# LED_12T-V2_0.net
KiCad netlist of a schematic drawn in Altium Designer
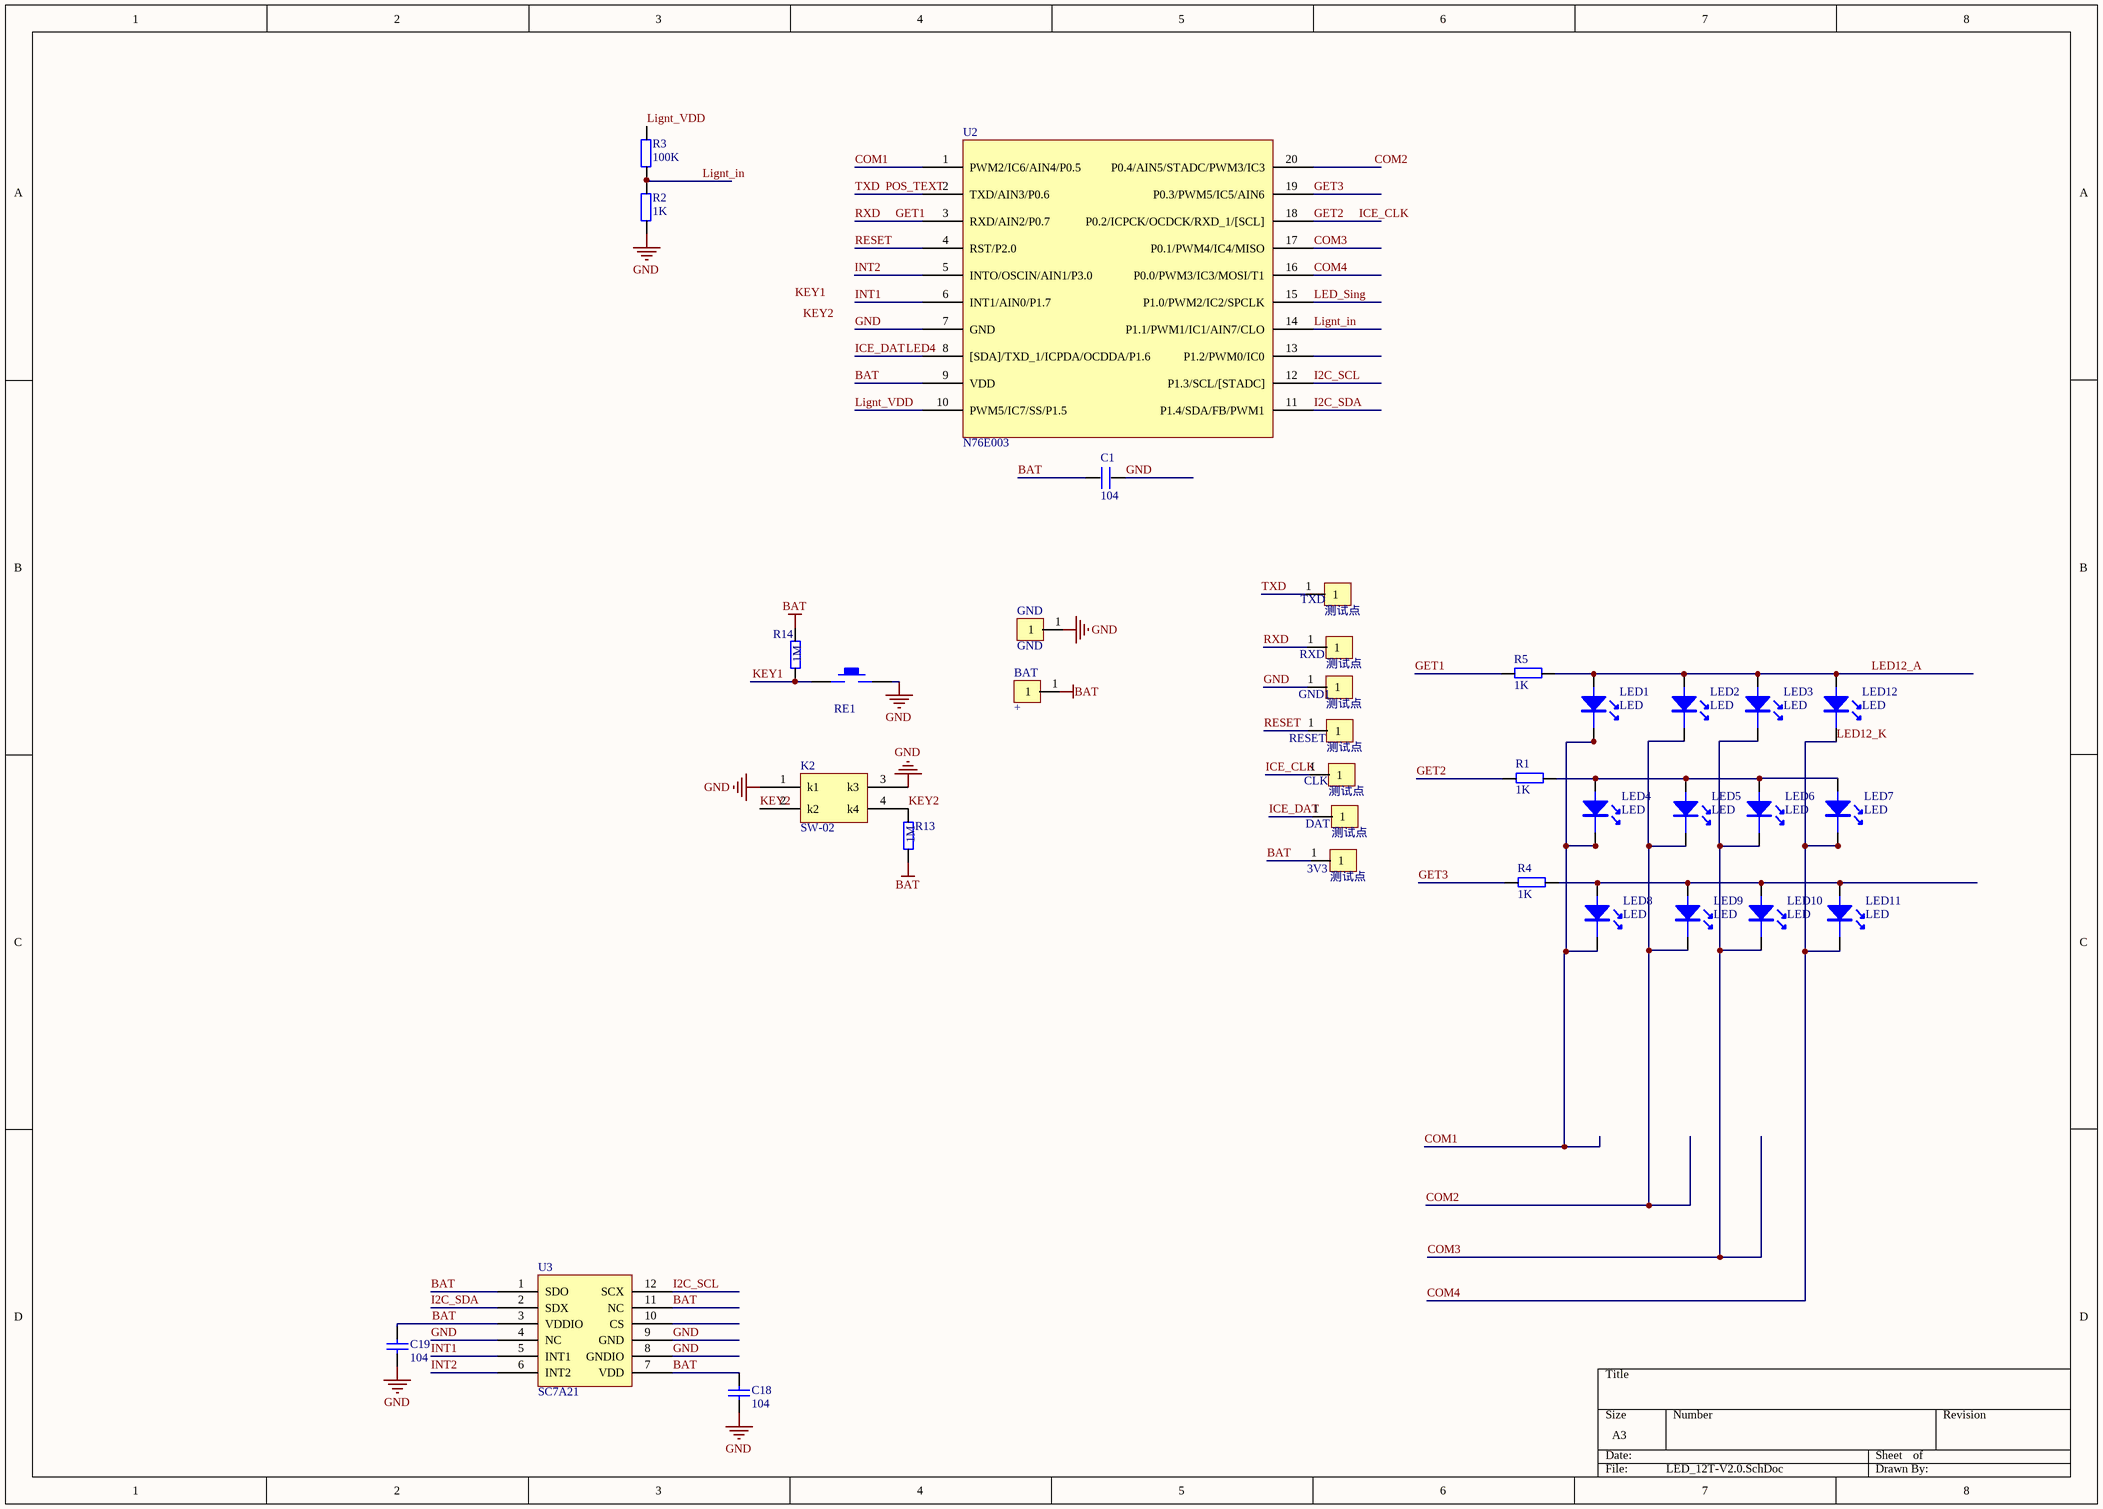
[diagram p0: LED_12T-V2.0.SchDoc]

(export (version "E")
  (design (tool "Eeschema 10.0.6"))
  (components
    (comp (ref "3V3") (value "测试点") (footprint "测试点") (libsource (lib "元件") (part "测试点")))
    (comp (ref "BAT") (value "+") (footprint "CR2450_Z") (libsource (lib "") (part "测试点_1")))
    (comp (ref "C1") (value "104") (footprint "0603P") (libsource (lib "3.5TFTLCD封装库") (part "C")))
    (comp (ref "C18")
      (value "104")
      (footprint "0402_C")
      (description "Capacitor")
      (fields (field (name "PUBLISHER") "Altium Limited"))
      (libsource (lib "Miscellaneous Devices") (part "Cap"))
    )
    (comp (ref "C19")
      (value "104")
      (footprint "0402_C")
      (description "Capacitor")
      (fields (field (name "PUBLISHER") "Altium Limited"))
      (libsource (lib "Miscellaneous Devices") (part "Cap"))
    )
    (comp (ref "CLK") (value "测试点") (footprint "测试点") (libsource (lib "元件") (part "测试点")))
    (comp (ref "DAT") (value "测试点") (footprint "测试点") (libsource (lib "元件") (part "测试点")))
    (comp (ref "GND") (value "GND") (footprint "测试点") (libsource (lib "") (part "测试点_1")))
    (comp (ref "GND1") (value "测试点") (footprint "测试点") (libsource (lib "元件") (part "测试点")))
    (comp (ref "K2") (value "SW-02") (footprint "四向滚珠开关") (libsource (lib "元件") (part "SW-02")))
    (comp (ref "LED1") (value "LED") (footprint "0402_LED") (libsource (lib "*") (part "LED")))
    (comp (ref "LED2") (value "LED") (footprint "0402_LED") (libsource (lib "*") (part "LED")))
    (comp (ref "LED3") (value "LED") (footprint "0402_LED") (libsource (lib "*") (part "LED")))
    (comp (ref "LED4") (value "LED") (footprint "0402_LED") (libsource (lib "*") (part "LED")))
    (comp (ref "LED5") (value "LED") (footprint "0402_LED") (libsource (lib "*") (part "LED")))
    (comp (ref "LED6") (value "LED") (footprint "0402_LED") (libsource (lib "*") (part "LED")))
    (comp (ref "LED7") (value "LED") (footprint "0402_LED") (libsource (lib "*") (part "LED")))
    (comp (ref "LED8") (value "LED") (footprint "0402_LED") (libsource (lib "*") (part "LED")))
    (comp (ref "LED9") (value "LED") (footprint "0402_LED") (libsource (lib "*") (part "LED")))
    (comp (ref "LED10") (value "LED") (footprint "0402_LED") (libsource (lib "*") (part "LED")))
    (comp (ref "LED11") (value "LED") (footprint "0402_LED") (libsource (lib "*") (part "LED")))
    (comp (ref "LED12") (value "LED") (footprint "0402_LED") (libsource (lib "*") (part "LED")))
    (comp (ref "R1")
      (value "1K")
      (footprint "自画库1:0603_R")
      (libsource (lib "Explorer STM32F407封装库") (part "R"))
    )
    (comp (ref "R2")
      (value "1K")
      (footprint "自画库1:0603_R")
      (libsource (lib "Explorer STM32F407封装库") (part "R"))
    )
    (comp (ref "R3")
      (value "100K")
      (footprint "自画库1:0402_R")
      (libsource (lib "Explorer STM32F407封装库") (part "R"))
    )
    (comp (ref "R4")
      (value "1K")
      (footprint "自画库1:0603_R")
      (libsource (lib "Explorer STM32F407封装库") (part "R"))
    )
    (comp (ref "R5")
      (value "1K")
      (footprint "自画库1:0603_R")
      (libsource (lib "Explorer STM32F407封装库") (part "R"))
    )
    (comp (ref "R13")
      (value "1M")
      (footprint "自画库1:0402_R")
      (libsource (lib "Explorer STM32F407封装库") (part "R"))
    )
    (comp (ref "R14")
      (value "1M")
      (footprint "自画库1:0402_R")
      (libsource (lib "Explorer STM32F407封装库") (part "R"))
    )
    (comp (ref "RE1")
      (value "KEY_M")
      (footprint "轻触开关 2x4")
      (libsource (lib "Explorer STM32F407封装库") (part "KEY_M"))
    )
    (comp (ref "RESET") (value "测试点") (footprint "测试点") (libsource (lib "元件") (part "测试点")))
    (comp (ref "RXD") (value "测试点") (footprint "测试点") (libsource (lib "元件") (part "测试点")))
    (comp (ref "TXD") (value "测试点") (footprint "测试点") (libsource (lib "元件") (part "测试点")))
    (comp (ref "U2") (value "N76E003") (footprint "STSOP20") (libsource (lib "元件") (part "N76E003")))
    (comp (ref "U3") (value "SC7A21") (footprint "自画库1:LGA-12-2*2*1") (libsource (lib "元件") (part "SC7A21")))
  )
  (nets
    (net (code "1") (name "/COM1") (class "Default")
      (node (ref "LED1") (pin "2") (pinfunction "K_2") (pintype "passive"))
      (node (ref "LED4") (pin "2") (pinfunction "K_2") (pintype "passive"))
      (node (ref "LED8") (pin "2") (pinfunction "K_2") (pintype "passive"))
      (node (ref "U2") (pin "1") (pinfunction "PWM2/IC6/AIN4/P0.5_1") (pintype "passive"))
    )
    (net (code "2") (name "/COM2") (class "Default")
      (node (ref "LED2") (pin "2") (pinfunction "K_2") (pintype "passive"))
      (node (ref "LED5") (pin "2") (pinfunction "K_2") (pintype "passive"))
      (node (ref "LED9") (pin "2") (pinfunction "K_2") (pintype "passive"))
      (node (ref "U2") (pin "20") (pinfunction "P0.4/AIN5/STADC/PWM3/IC3_20") (pintype "passive"))
    )
    (net (code "3") (name "/COM3") (class "Default")
      (node (ref "LED10") (pin "2") (pinfunction "K_2") (pintype "passive"))
      (node (ref "LED3") (pin "2") (pinfunction "K_2") (pintype "passive"))
      (node (ref "LED6") (pin "2") (pinfunction "K_2") (pintype "passive"))
      (node (ref "U2") (pin "17") (pinfunction "P0.1/PWM4/IC4/MISO_17") (pintype "passive"))
    )
    (net (code "4") (name "/COM4") (class "Default")
      (node (ref "LED11") (pin "2") (pinfunction "K_2") (pintype "passive"))
      (node (ref "LED12") (pin "2") (pinfunction "K_2") (pintype "passive"))
      (node (ref "LED7") (pin "2") (pinfunction "K_2") (pintype "passive"))
      (node (ref "U2") (pin "16") (pinfunction "P0.0/PWM3/IC3/MOSI/T1_16") (pintype "passive"))
    )
    (net (code "5") (name "/GET1") (class "Default")
      (node (ref "R5") (pin "2") (pintype "passive"))
      (node (ref "RXD") (pin "1") (pinfunction "1_1") (pintype "passive"))
      (node (ref "U2") (pin "3") (pinfunction "RXD/AIN2/P0.7_3") (pintype "passive"))
    )
    (net (code "6") (name "/GET2") (class "Default")
      (node (ref "CLK") (pin "1") (pinfunction "1_1") (pintype "passive"))
      (node (ref "R1") (pin "2") (pintype "passive"))
      (node (ref "U2") (pin "18") (pinfunction "P0.2/ICPCK/OCDCK/RXD_1/[SCL]_18") (pintype "passive"))
    )
    (net (code "7") (name "/GET3") (class "Default")
      (node (ref "R4") (pin "2") (pintype "passive"))
      (node (ref "U2") (pin "19") (pinfunction "P0.3/PWM5/IC5/AIN6_19") (pintype "passive"))
    )
    (net (code "8") (name "/I2C_SCL") (class "Default")
      (node (ref "U2") (pin "12") (pinfunction "P1.3/SCL/[STADC]_12") (pintype "passive"))
      (node (ref "U3") (pin "12") (pinfunction "SCX_12") (pintype "passive"))
    )
    (net (code "9") (name "/I2C_SDA") (class "Default")
      (node (ref "U2") (pin "11") (pinfunction "P1.4/SDA/FB/PWM1_11") (pintype "passive"))
      (node (ref "U3") (pin "2") (pinfunction "SDX_2") (pintype "passive"))
    )
    (net (code "10") (name "/ICE_DAT") (class "Default")
      (node (ref "DAT") (pin "1") (pinfunction "1_1") (pintype "passive"))
      (node (ref "U2") (pin "8") (pinfunction "[SDA]/TXD_1/ICPDA/OCDDA/P1.6_8") (pintype "passive"))
    )
    (net (code "11") (name "/INT1") (class "Default")
      (node (ref "U2") (pin "6") (pinfunction "INT1/AIN0/P1.7_6") (pintype "passive"))
      (node (ref "U3") (pin "5") (pinfunction "INT1_5") (pintype "passive"))
    )
    (net (code "12") (name "/INT2") (class "Default")
      (node (ref "U2") (pin "5") (pinfunction "INTO/OSCIN/AIN1/P3.0_5") (pintype "passive"))
      (node (ref "U3") (pin "6") (pinfunction "INT2_6") (pintype "passive"))
    )
    (net (code "13") (name "/KEY1") (class "Default")
      (node (ref "R14") (pin "1") (pintype "passive"))
      (node (ref "RE1") (pin "1") (pinfunction "1_1") (pintype "passive"))
    )
    (net (code "14") (name "/KEY2") (class "Default")
      (node (ref "K2") (pin "2") (pinfunction "k2_2") (pintype "passive"))
      (node (ref "K2") (pin "4") (pinfunction "k4_4") (pintype "passive"))
      (node (ref "R13") (pin "2") (pintype "passive"))
    )
    (net (code "15") (name "/LED12_A") (class "Default")
      (node (ref "LED1") (pin "1") (pinfunction "A_1") (pintype "passive"))
      (node (ref "LED12") (pin "1") (pinfunction "A_1") (pintype "passive"))
      (node (ref "LED2") (pin "1") (pinfunction "A_1") (pintype "passive"))
      (node (ref "LED3") (pin "1") (pinfunction "A_1") (pintype "passive"))
      (node (ref "R5") (pin "1") (pintype "passive"))
    )
    (net (code "16") (name "/LED_Sing") (class "Default")
      (node (ref "U2") (pin "15") (pinfunction "P1.0/PWM2/IC2/SPCLK_15") (pintype "passive"))
    )
    (net (code "17") (name "/Lignt_VDD") (class "Default")
      (node (ref "R3") (pin "1") (pintype "passive"))
      (node (ref "U2") (pin "10") (pinfunction "PWM5/IC7/SS/P1.5_10") (pintype "passive"))
    )
    (net (code "18") (name "/Lignt_in") (class "Default")
      (node (ref "R2") (pin "1") (pintype "passive"))
      (node (ref "R3") (pin "2") (pintype "passive"))
      (node (ref "U2") (pin "14") (pinfunction "P1.1/PWM1/IC1/AIN7/CLO_14") (pintype "passive"))
    )
    (net (code "19") (name "/POS_TEXT") (class "Default")
      (node (ref "TXD") (pin "1") (pinfunction "1_1") (pintype "passive"))
      (node (ref "U2") (pin "2") (pinfunction "TXD/AIN3/P0.6_2") (pintype "passive"))
    )
    (net (code "20") (name "/RESET") (class "Default")
      (node (ref "RESET") (pin "1") (pinfunction "1_1") (pintype "passive"))
      (node (ref "U2") (pin "4") (pinfunction "RST/P2.0_4") (pintype "passive"))
    )
    (net (code "21") (name "BAT") (class "Default")
      (node (ref "3V3") (pin "1") (pinfunction "1_1") (pintype "passive"))
      (node (ref "BAT") (pin "1") (pinfunction "1_1") (pintype "passive"))
      (node (ref "C1") (pin "2") (pintype "passive"))
      (node (ref "C18") (pin "1") (pinfunction "1_1") (pintype "passive"))
      (node (ref "C19") (pin "1") (pinfunction "1_1") (pintype "passive"))
      (node (ref "R13") (pin "1") (pintype "passive"))
      (node (ref "R14") (pin "2") (pintype "passive"))
      (node (ref "U2") (pin "9") (pinfunction "VDD_9") (pintype "passive"))
      (node (ref "U3") (pin "1") (pinfunction "SDO_1") (pintype "passive"))
      (node (ref "U3") (pin "11") (pinfunction "NC_11") (pintype "passive"))
      (node (ref "U3") (pin "3") (pinfunction "VDDIO_3") (pintype "passive"))
      (node (ref "U3") (pin "7") (pinfunction "VDD_7") (pintype "passive"))
    )
    (net (code "22") (name "GND") (class "Default")
      (node (ref "C1") (pin "1") (pintype "passive"))
      (node (ref "C18") (pin "2") (pinfunction "2_2") (pintype "passive"))
      (node (ref "C19") (pin "2") (pinfunction "2_2") (pintype "passive"))
      (node (ref "GND") (pin "1") (pinfunction "1_1") (pintype "passive"))
      (node (ref "GND1") (pin "1") (pinfunction "1_1") (pintype "passive"))
      (node (ref "K2") (pin "1") (pinfunction "k1_1") (pintype "passive"))
      (node (ref "K2") (pin "3") (pinfunction "k3_3") (pintype "passive"))
      (node (ref "R2") (pin "2") (pintype "passive"))
      (node (ref "RE1") (pin "2") (pinfunction "2_2") (pintype "passive"))
      (node (ref "U2") (pin "7") (pinfunction "GND_7") (pintype "passive"))
      (node (ref "U3") (pin "4") (pinfunction "NC_4") (pintype "passive"))
      (node (ref "U3") (pin "8") (pinfunction "GNDIO_8") (pintype "passive"))
      (node (ref "U3") (pin "9") (pinfunction "GND_9") (pintype "passive"))
    )
    (net (code "23") (name "Net-(LED4-A)") (class "Default")
      (node (ref "LED4") (pin "1") (pinfunction "A_1") (pintype "passive"))
      (node (ref "LED5") (pin "1") (pinfunction "A_1") (pintype "passive"))
      (node (ref "LED6") (pin "1") (pinfunction "A_1") (pintype "passive"))
      (node (ref "LED7") (pin "1") (pinfunction "A_1") (pintype "passive"))
      (node (ref "R1") (pin "1") (pintype "passive"))
    )
    (net (code "24") (name "Net-(LED10-A)") (class "Default")
      (node (ref "LED10") (pin "1") (pinfunction "A_1") (pintype "passive"))
      (node (ref "LED11") (pin "1") (pinfunction "A_1") (pintype "passive"))
      (node (ref "LED8") (pin "1") (pinfunction "A_1") (pintype "passive"))
      (node (ref "LED9") (pin "1") (pinfunction "A_1") (pintype "passive"))
      (node (ref "R4") (pin "1") (pintype "passive"))
    )
    (net (code "25") (name "unconnected-(U2-P1.2{slash}PWM0{slash}IC0-Pad13)") (class "Default")
      (node (ref "U2") (pin "13") (pinfunction "P1.2/PWM0/IC0_13") (pintype "passive"))
    )
    (net (code "26") (name "unconnected-(U3-CS-Pad10)") (class "Default")
      (node (ref "U3") (pin "10") (pinfunction "CS_10") (pintype "passive"))
    )
  )
)
